# loki_mod.net
KiCad netlist of a schematic drawn in EAGLE
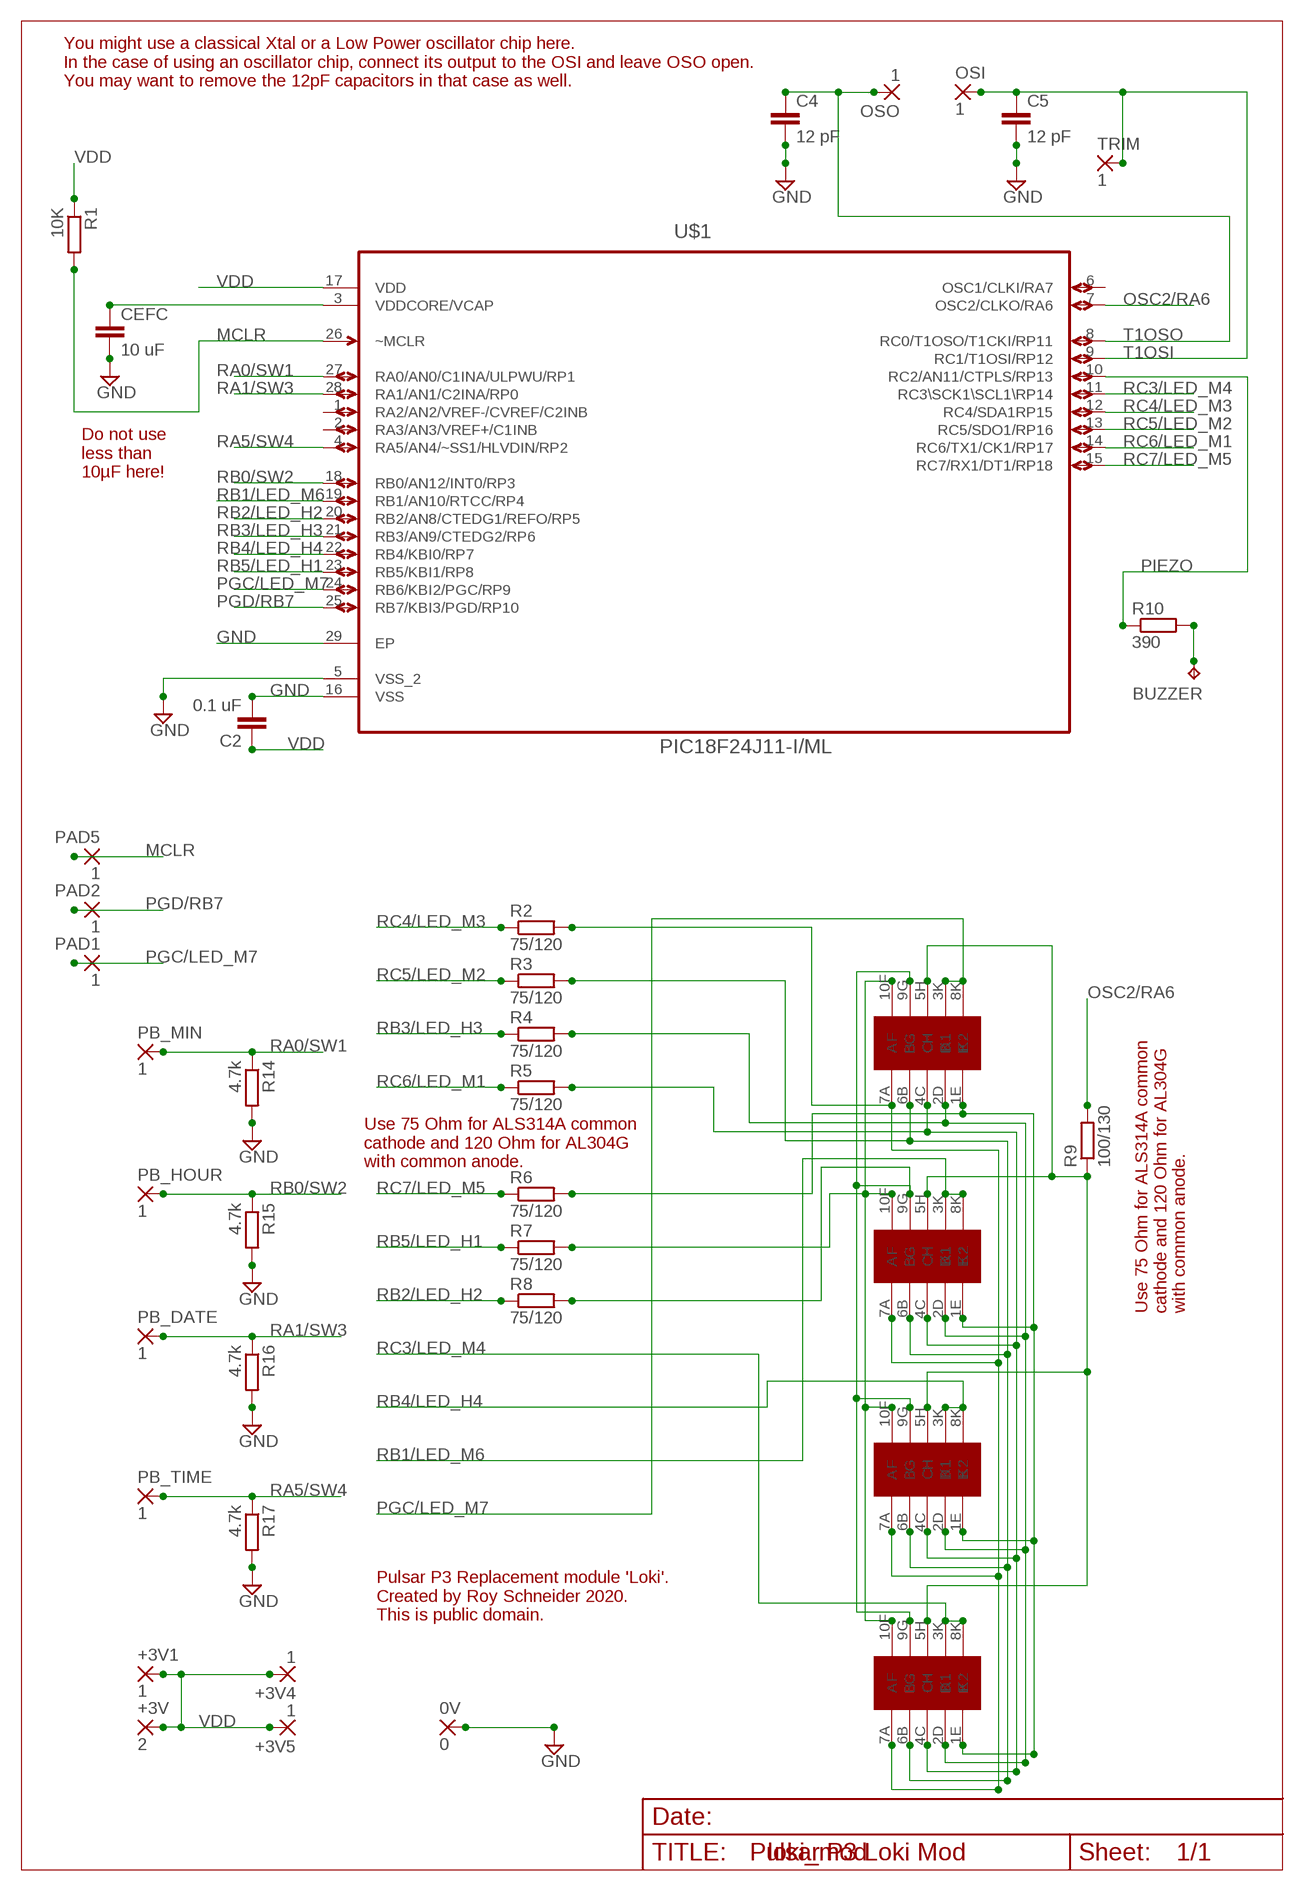
[diagram p0: schematic, sheet 1]

(export (version "E")
  (design (tool "Eeschema 10.0.6"))
  (components
    (comp (ref "+3V")
      (value "2")
      (footprint "eagle-import:SMD1,27-2,54")
      (libsource (lib "eagle-import") (part "SMD2"))
    )
    (comp (ref "+3V1")
      (value "1")
      (footprint "eagle-import:SMD1,27-2,54")
      (libsource (lib "eagle-import") (part "SMD2"))
    )
    (comp (ref "+3V4")
      (value "1")
      (footprint "eagle-import:SMD1,27-2,54")
      (libsource (lib "eagle-import") (part "SMD2"))
    )
    (comp (ref "+3V5")
      (value "1")
      (footprint "eagle-import:SMD1,27-2,54")
      (libsource (lib "eagle-import") (part "SMD2"))
    )
    (comp (ref "0V")
      (value "0")
      (footprint "eagle-import:SMD1,27-2,54")
      (libsource (lib "eagle-import") (part "SMD2"))
    )
    (comp (ref "1H")
      (value "L104G")
      (footprint "eagle-import:L104G")
      (libsource (lib "eagle-import") (part "L104G"))
    )
    (comp (ref "1M")
      (value "L104G")
      (footprint "eagle-import:L104G")
      (libsource (lib "eagle-import") (part "L104G"))
    )
    (comp (ref "10H")
      (value "L104G")
      (footprint "eagle-import:L104G")
      (libsource (lib "eagle-import") (part "L104G"))
    )
    (comp (ref "10M")
      (value "L104G")
      (footprint "eagle-import:L104G")
      (libsource (lib "eagle-import") (part "L104G"))
    )
    (comp (ref "BUZZER")
      (value "TPTP06SQ")
      (footprint "eagle-import:TP06SQ")
      (libsource (lib "eagle-import") (part "TPTP06SQ"))
    )
    (comp (ref "C2")
      (value "0.1 uF")
      (footprint "eagle-import:C0603")
      (libsource (lib "eagle-import") (part "C-EUC0603"))
    )
    (comp (ref "C4")
      (value "12 pF")
      (footprint "eagle-import:C0603")
      (libsource (lib "eagle-import") (part "C-EUC0603"))
    )
    (comp (ref "C5")
      (value "12 pF")
      (footprint "eagle-import:C0603")
      (libsource (lib "eagle-import") (part "C-EUC0603"))
    )
    (comp (ref "CEFC")
      (value "10 uF")
      (footprint "eagle-import:C0603")
      (libsource (lib "eagle-import") (part "C-EUC0603"))
    )
    (comp (ref "OSI")
      (value "1")
      (footprint "eagle-import:SMD1,27-2,54")
      (libsource (lib "eagle-import") (part "SMD2"))
    )
    (comp (ref "OSO")
      (value "1")
      (footprint "eagle-import:SMD1,27-2,54")
      (libsource (lib "eagle-import") (part "SMD2"))
    )
    (comp (ref "PAD1")
      (value "1")
      (footprint "eagle-import:SMD1,27-2,54")
      (libsource (lib "eagle-import") (part "SMD2"))
    )
    (comp (ref "PAD2")
      (value "1")
      (footprint "eagle-import:SMD1,27-2,54")
      (libsource (lib "eagle-import") (part "SMD2"))
    )
    (comp (ref "PAD5")
      (value "1")
      (footprint "eagle-import:SMD1,27-2,54")
      (libsource (lib "eagle-import") (part "SMD2"))
    )
    (comp (ref "PB_DATE")
      (value "1")
      (footprint "eagle-import:SMD1,27-2,54")
      (libsource (lib "eagle-import") (part "SMD2"))
    )
    (comp (ref "PB_HOUR")
      (value "1")
      (footprint "eagle-import:SMD1,27-2,54")
      (libsource (lib "eagle-import") (part "SMD2"))
    )
    (comp (ref "PB_MIN")
      (value "1")
      (footprint "eagle-import:SMD1,27-2,54")
      (libsource (lib "eagle-import") (part "SMD2"))
    )
    (comp (ref "PB_TIME")
      (value "1")
      (footprint "eagle-import:SMD1,27-2,54")
      (libsource (lib "eagle-import") (part "SMD2"))
    )
    (comp (ref "R1")
      (value "10K")
      (footprint "eagle-import:R0402")
      (libsource (lib "eagle-import") (part "R-EU_R0402"))
    )
    (comp (ref "R2")
      (value "75/120")
      (footprint "eagle-import:R0402")
      (libsource (lib "eagle-import") (part "resistor_R-EU_R0402"))
    )
    (comp (ref "R3")
      (value "75/120")
      (footprint "eagle-import:R0402")
      (libsource (lib "eagle-import") (part "resistor_R-EU_R0402"))
    )
    (comp (ref "R4")
      (value "75/120")
      (footprint "eagle-import:R0402")
      (libsource (lib "eagle-import") (part "resistor_R-EU_R0402"))
    )
    (comp (ref "R5")
      (value "75/120")
      (footprint "eagle-import:R0402")
      (libsource (lib "eagle-import") (part "resistor_R-EU_R0402"))
    )
    (comp (ref "R6")
      (value "75/120")
      (footprint "eagle-import:R0402")
      (libsource (lib "eagle-import") (part "resistor_R-EU_R0402"))
    )
    (comp (ref "R7")
      (value "75/120")
      (footprint "eagle-import:R0402")
      (libsource (lib "eagle-import") (part "resistor_R-EU_R0402"))
    )
    (comp (ref "R8")
      (value "75/120")
      (footprint "eagle-import:R0402")
      (libsource (lib "eagle-import") (part "resistor_R-EU_R0402"))
    )
    (comp (ref "R9")
      (value "100/130")
      (footprint "eagle-import:R0402")
      (libsource (lib "eagle-import") (part "resistor_R-EU_R0402"))
    )
    (comp (ref "R10")
      (value "390")
      (footprint "eagle-import:R0402")
      (libsource (lib "eagle-import") (part "resistor_R-EU_R0402"))
    )
    (comp (ref "R14")
      (value "4.7k")
      (footprint "eagle-import:R0402")
      (libsource (lib "eagle-import") (part "resistor_R-EU_R0402"))
    )
    (comp (ref "R15")
      (value "4.7k")
      (footprint "eagle-import:R0402")
      (libsource (lib "eagle-import") (part "resistor_R-EU_R0402"))
    )
    (comp (ref "R16")
      (value "4.7k")
      (footprint "eagle-import:R0402")
      (libsource (lib "eagle-import") (part "resistor_R-EU_R0402"))
    )
    (comp (ref "R17")
      (value "4.7k")
      (footprint "eagle-import:R0402")
      (libsource (lib "eagle-import") (part "resistor_R-EU_R0402"))
    )
    (comp (ref "TRIM")
      (value "1")
      (footprint "eagle-import:SMD1,27-2,54")
      (libsource (lib "eagle-import") (part "SMD2"))
    )
    (comp (ref "U$1")
      (value "PIC18F24J11-I/ML")
      (footprint "eagle-import:QFN65P600X600X100-29N")
      (fields (field (name "MPN") "PIC18F24J11-I/Ml"))
      (libsource (lib "eagle-import") (part "PIC18F24J11-I/ML"))
    )
  )
  (nets
    (net (code "1") (name "/MCLR") (class "Default")
      (node (ref "PAD5") (pin "1") (pinfunction "P_1") (pintype "passive"))
      (node (ref "R1") (pin "2") (pinfunction "2_2") (pintype "passive"))
      (node (ref "U$1") (pin "26") (pinfunction "~{MCLR}_26") (pintype "input"))
    )
    (net (code "2") (name "/OSC2{slash}RA6") (class "Default")
      (node (ref "R9") (pin "2") (pinfunction "2_2") (pintype "passive"))
      (node (ref "U$1") (pin "7") (pinfunction "OSC2/CLKO/RA6_7") (pintype "bidirectional"))
    )
    (net (code "3") (name "/PGC{slash}LED_M7") (class "Default")
      (node (ref "10H") (pin "3K") (pinfunction "K1_3K") (pintype "bidirectional"))
      (node (ref "10H") (pin "8K") (pinfunction "K2_8K") (pintype "bidirectional"))
      (node (ref "PAD1") (pin "1") (pinfunction "P_1") (pintype "passive"))
      (node (ref "U$1") (pin "24") (pinfunction "RB6/KBI2/PGC/RP9_24") (pintype "bidirectional"))
    )
    (net (code "4") (name "/PGD{slash}RB7") (class "Default")
      (node (ref "PAD2") (pin "1") (pinfunction "P_1") (pintype "passive"))
      (node (ref "U$1") (pin "25") (pinfunction "RB7/KBI3/PGD/RP10_25") (pintype "bidirectional"))
    )
    (net (code "5") (name "/PIEZO") (class "Default")
      (node (ref "R10") (pin "1") (pinfunction "1_1") (pintype "passive"))
      (node (ref "U$1") (pin "10") (pinfunction "RC2/AN11/CTPLS/RP13_10") (pintype "bidirectional"))
    )
    (net (code "6") (name "/RA0{slash}SW1") (class "Default")
      (node (ref "PB_MIN") (pin "1") (pinfunction "P_1") (pintype "passive"))
      (node (ref "R14") (pin "1") (pinfunction "1_1") (pintype "passive"))
      (node (ref "U$1") (pin "27") (pinfunction "RA0/AN0/C1INA/ULPWU/RP1_27") (pintype "bidirectional"))
    )
    (net (code "7") (name "/RA1{slash}SW3") (class "Default")
      (node (ref "PB_DATE") (pin "1") (pinfunction "P_1") (pintype "passive"))
      (node (ref "R16") (pin "1") (pinfunction "1_1") (pintype "passive"))
      (node (ref "U$1") (pin "28") (pinfunction "RA1/AN1/C2INA/RP0_28") (pintype "bidirectional"))
    )
    (net (code "8") (name "/RA5{slash}SW4") (class "Default")
      (node (ref "PB_TIME") (pin "1") (pinfunction "P_1") (pintype "passive"))
      (node (ref "R17") (pin "1") (pinfunction "1_1") (pintype "passive"))
      (node (ref "U$1") (pin "4") (pinfunction "RA5/AN4/~{SS1/HLVDIN/RP2}_4") (pintype "bidirectional"))
    )
    (net (code "9") (name "/RB0{slash}SW2") (class "Default")
      (node (ref "PB_HOUR") (pin "1") (pinfunction "P_1") (pintype "passive"))
      (node (ref "R15") (pin "1") (pinfunction "1_1") (pintype "passive"))
      (node (ref "U$1") (pin "18") (pinfunction "RB0/AN12/INT0/RP3_18") (pintype "bidirectional"))
    )
    (net (code "10") (name "/RB1{slash}LED_M6") (class "Default")
      (node (ref "1H") (pin "3K") (pinfunction "K1_3K") (pintype "bidirectional"))
      (node (ref "1H") (pin "8K") (pinfunction "K2_8K") (pintype "bidirectional"))
      (node (ref "U$1") (pin "19") (pinfunction "RB1/AN10/RTCC/RP4_19") (pintype "bidirectional"))
    )
    (net (code "11") (name "/RB2{slash}LED_H2") (class "Default")
      (node (ref "R8") (pin "1") (pinfunction "1_1") (pintype "passive"))
      (node (ref "U$1") (pin "20") (pinfunction "RB2/AN8/CTEDG1/REFO/RP5_20") (pintype "bidirectional"))
    )
    (net (code "12") (name "/RB3{slash}LED_H3") (class "Default")
      (node (ref "R4") (pin "1") (pinfunction "1_1") (pintype "passive"))
      (node (ref "U$1") (pin "21") (pinfunction "RB3/AN9/CTEDG2/RP6_21") (pintype "bidirectional"))
    )
    (net (code "13") (name "/RB4{slash}LED_H4") (class "Default")
      (node (ref "10M") (pin "3K") (pinfunction "K1_3K") (pintype "bidirectional"))
      (node (ref "10M") (pin "8K") (pinfunction "K2_8K") (pintype "bidirectional"))
      (node (ref "U$1") (pin "22") (pinfunction "RB4/KBI0/RP7_22") (pintype "bidirectional"))
    )
    (net (code "14") (name "/RB5{slash}LED_H1") (class "Default")
      (node (ref "R7") (pin "1") (pinfunction "1_1") (pintype "passive"))
      (node (ref "U$1") (pin "23") (pinfunction "RB5/KBI1/RP8_23") (pintype "bidirectional"))
    )
    (net (code "15") (name "/RC3{slash}LED_M4") (class "Default")
      (node (ref "1M") (pin "3K") (pinfunction "K1_3K") (pintype "bidirectional"))
      (node (ref "1M") (pin "8K") (pinfunction "K2_8K") (pintype "bidirectional"))
      (node (ref "U$1") (pin "11") (pinfunction "RC3\\SCK1\\SCL1\\RP14_11") (pintype "bidirectional"))
    )
    (net (code "16") (name "/RC4{slash}LED_M3") (class "Default")
      (node (ref "R2") (pin "1") (pinfunction "1_1") (pintype "passive"))
      (node (ref "U$1") (pin "12") (pinfunction "RC4/SDA1RP15_12") (pintype "bidirectional"))
    )
    (net (code "17") (name "/RC5{slash}LED_M2") (class "Default")
      (node (ref "R3") (pin "1") (pinfunction "1_1") (pintype "passive"))
      (node (ref "U$1") (pin "13") (pinfunction "RC5/SDO1/RP16_13") (pintype "bidirectional"))
    )
    (net (code "18") (name "/RC6{slash}LED_M1") (class "Default")
      (node (ref "R5") (pin "1") (pinfunction "1_1") (pintype "passive"))
      (node (ref "U$1") (pin "14") (pinfunction "RC6/TX1/CK1/RP17_14") (pintype "bidirectional"))
    )
    (net (code "19") (name "/RC7{slash}LED_M5") (class "Default")
      (node (ref "R6") (pin "1") (pinfunction "1_1") (pintype "passive"))
      (node (ref "U$1") (pin "15") (pinfunction "RC7/RX1/DT1/RP18_15") (pintype "bidirectional"))
    )
    (net (code "20") (name "/T1OSI") (class "Default")
      (node (ref "C5") (pin "1") (pinfunction "1_1") (pintype "passive"))
      (node (ref "OSI") (pin "1") (pinfunction "P_1") (pintype "passive"))
      (node (ref "TRIM") (pin "1") (pinfunction "P_1") (pintype "passive"))
      (node (ref "U$1") (pin "9") (pinfunction "RC1/T1OSI/RP12_9") (pintype "bidirectional"))
    )
    (net (code "21") (name "/T1OSO") (class "Default")
      (node (ref "C4") (pin "1") (pinfunction "1_1") (pintype "passive"))
      (node (ref "OSO") (pin "1") (pinfunction "P_1") (pintype "passive"))
      (node (ref "U$1") (pin "8") (pinfunction "RC0/T1OSO/T1CKI/RP11_8") (pintype "bidirectional"))
    )
    (net (code "22") (name "/VDD") (class "Default")
      (node (ref "+3V") (pin "1") (pinfunction "P_1") (pintype "passive"))
      (node (ref "+3V1") (pin "1") (pinfunction "P_1") (pintype "passive"))
      (node (ref "+3V4") (pin "1") (pinfunction "P_1") (pintype "passive"))
      (node (ref "+3V5") (pin "1") (pinfunction "P_1") (pintype "passive"))
      (node (ref "C2") (pin "1") (pinfunction "1_1") (pintype "passive"))
      (node (ref "R1") (pin "1") (pinfunction "1_1") (pintype "passive"))
      (node (ref "U$1") (pin "17") (pinfunction "VDD_17") (pintype "power_in"))
    )
    (net (code "23") (name "GND") (class "Default")
      (node (ref "0V") (pin "1") (pinfunction "P_1") (pintype "passive"))
      (node (ref "C2") (pin "2") (pinfunction "2_2") (pintype "passive"))
      (node (ref "C4") (pin "2") (pinfunction "2_2") (pintype "passive"))
      (node (ref "C5") (pin "2") (pinfunction "2_2") (pintype "passive"))
      (node (ref "CEFC") (pin "2") (pinfunction "2_2") (pintype "passive"))
      (node (ref "R14") (pin "2") (pinfunction "2_2") (pintype "passive"))
      (node (ref "R15") (pin "2") (pinfunction "2_2") (pintype "passive"))
      (node (ref "R16") (pin "2") (pinfunction "2_2") (pintype "passive"))
      (node (ref "R17") (pin "2") (pinfunction "2_2") (pintype "passive"))
      (node (ref "U$1") (pin "16") (pinfunction "VSS_16") (pintype "passive"))
      (node (ref "U$1") (pin "29") (pinfunction "EP_29") (pintype "passive"))
      (node (ref "U$1") (pin "5") (pinfunction "VSS_2_5") (pintype "passive"))
    )
    (net (code "24") (name "Net-(10H-A)") (class "Default")
      (node (ref "10H") (pin "7A") (pinfunction "A_7A") (pintype "bidirectional"))
      (node (ref "10M") (pin "7A") (pinfunction "A_7A") (pintype "bidirectional"))
      (node (ref "1H") (pin "7A") (pinfunction "A_7A") (pintype "bidirectional"))
      (node (ref "1M") (pin "7A") (pinfunction "A_7A") (pintype "bidirectional"))
      (node (ref "R2") (pin "2") (pinfunction "2_2") (pintype "passive"))
    )
    (net (code "25") (name "Net-(10H-B)") (class "Default")
      (node (ref "10H") (pin "6B") (pinfunction "B_6B") (pintype "bidirectional"))
      (node (ref "10M") (pin "6B") (pinfunction "B_6B") (pintype "bidirectional"))
      (node (ref "1H") (pin "6B") (pinfunction "B_6B") (pintype "bidirectional"))
      (node (ref "1M") (pin "6B") (pinfunction "B_6B") (pintype "bidirectional"))
      (node (ref "R3") (pin "2") (pinfunction "2_2") (pintype "passive"))
    )
    (net (code "26") (name "Net-(10H-C)") (class "Default")
      (node (ref "10H") (pin "4C") (pinfunction "C_4C") (pintype "bidirectional"))
      (node (ref "10M") (pin "4C") (pinfunction "C_4C") (pintype "bidirectional"))
      (node (ref "1H") (pin "4C") (pinfunction "C_4C") (pintype "bidirectional"))
      (node (ref "1M") (pin "4C") (pinfunction "C_4C") (pintype "bidirectional"))
      (node (ref "R5") (pin "2") (pinfunction "2_2") (pintype "passive"))
    )
    (net (code "27") (name "Net-(10H-D)") (class "Default")
      (node (ref "10H") (pin "2D") (pinfunction "D_2D") (pintype "bidirectional"))
      (node (ref "10M") (pin "2D") (pinfunction "D_2D") (pintype "bidirectional"))
      (node (ref "1H") (pin "2D") (pinfunction "D_2D") (pintype "bidirectional"))
      (node (ref "1M") (pin "2D") (pinfunction "D_2D") (pintype "bidirectional"))
      (node (ref "R4") (pin "2") (pinfunction "2_2") (pintype "passive"))
    )
    (net (code "28") (name "Net-(10H-E)") (class "Default")
      (node (ref "10H") (pin "1E") (pinfunction "E_1E") (pintype "bidirectional"))
      (node (ref "10M") (pin "1E") (pinfunction "E_1E") (pintype "bidirectional"))
      (node (ref "1H") (pin "1E") (pinfunction "E_1E") (pintype "bidirectional"))
      (node (ref "1M") (pin "1E") (pinfunction "E_1E") (pintype "bidirectional"))
      (node (ref "R6") (pin "2") (pinfunction "2_2") (pintype "passive"))
    )
    (net (code "29") (name "Net-(10H-F)") (class "Default")
      (node (ref "10H") (pin "10F") (pinfunction "F_10F") (pintype "bidirectional"))
      (node (ref "10M") (pin "10F") (pinfunction "F_10F") (pintype "bidirectional"))
      (node (ref "1H") (pin "10F") (pinfunction "F_10F") (pintype "bidirectional"))
      (node (ref "1M") (pin "10F") (pinfunction "F_10F") (pintype "bidirectional"))
      (node (ref "R7") (pin "2") (pinfunction "2_2") (pintype "passive"))
    )
    (net (code "30") (name "Net-(10H-G)") (class "Default")
      (node (ref "10H") (pin "9G") (pinfunction "G_9G") (pintype "bidirectional"))
      (node (ref "10M") (pin "9G") (pinfunction "G_9G") (pintype "bidirectional"))
      (node (ref "1H") (pin "9G") (pinfunction "G_9G") (pintype "bidirectional"))
      (node (ref "1M") (pin "9G") (pinfunction "G_9G") (pintype "bidirectional"))
      (node (ref "R8") (pin "2") (pinfunction "2_2") (pintype "passive"))
    )
    (net (code "31") (name "Net-(10H-H)") (class "Default")
      (node (ref "10H") (pin "5H") (pinfunction "H_5H") (pintype "bidirectional"))
      (node (ref "10M") (pin "5H") (pinfunction "H_5H") (pintype "bidirectional"))
      (node (ref "1H") (pin "5H") (pinfunction "H_5H") (pintype "bidirectional"))
      (node (ref "1M") (pin "5H") (pinfunction "H_5H") (pintype "bidirectional"))
      (node (ref "R9") (pin "1") (pinfunction "1_1") (pintype "passive"))
    )
    (net (code "32") (name "Net-(BUZZER-PadTP)") (class "Default")
      (node (ref "BUZZER") (pin "TP") (pinfunction "TP_TP") (pintype "input"))
      (node (ref "R10") (pin "2") (pinfunction "2_2") (pintype "passive"))
    )
    (net (code "33") (name "Net-(U$1-VDDCORE{slash}VCAP)") (class "Default")
      (node (ref "CEFC") (pin "1") (pinfunction "1_1") (pintype "passive"))
      (node (ref "U$1") (pin "3") (pinfunction "VDDCORE/VCAP_3") (pintype "power_in"))
    )
    (net (code "34") (name "unconnected-(U$1-OSC1{slash}CLKI{slash}RA7-Pad6)") (class "Default")
      (node (ref "U$1") (pin "6") (pinfunction "OSC1/CLKI/RA7_6") (pintype "bidirectional"))
    )
    (net (code "35") (name "unconnected-(U$1-RA2{slash}AN2{slash}VREF-{slash}CVREF{slash}C2INB-Pad1)") (class "Default")
      (node (ref "U$1") (pin "1") (pinfunction "RA2/AN2/VREF-/CVREF/C2INB_1") (pintype "bidirectional"))
    )
    (net (code "36") (name "unconnected-(U$1-RA3{slash}AN3{slash}VREF+{slash}C1INB-Pad2)") (class "Default")
      (node (ref "U$1") (pin "2") (pinfunction "RA3/AN3/VREF+/C1INB_2") (pintype "bidirectional"))
    )
  )
)
